# KCInput_Attenuator_V0_2.net
KiCad netlist of a schematic drawn in Altium Designer
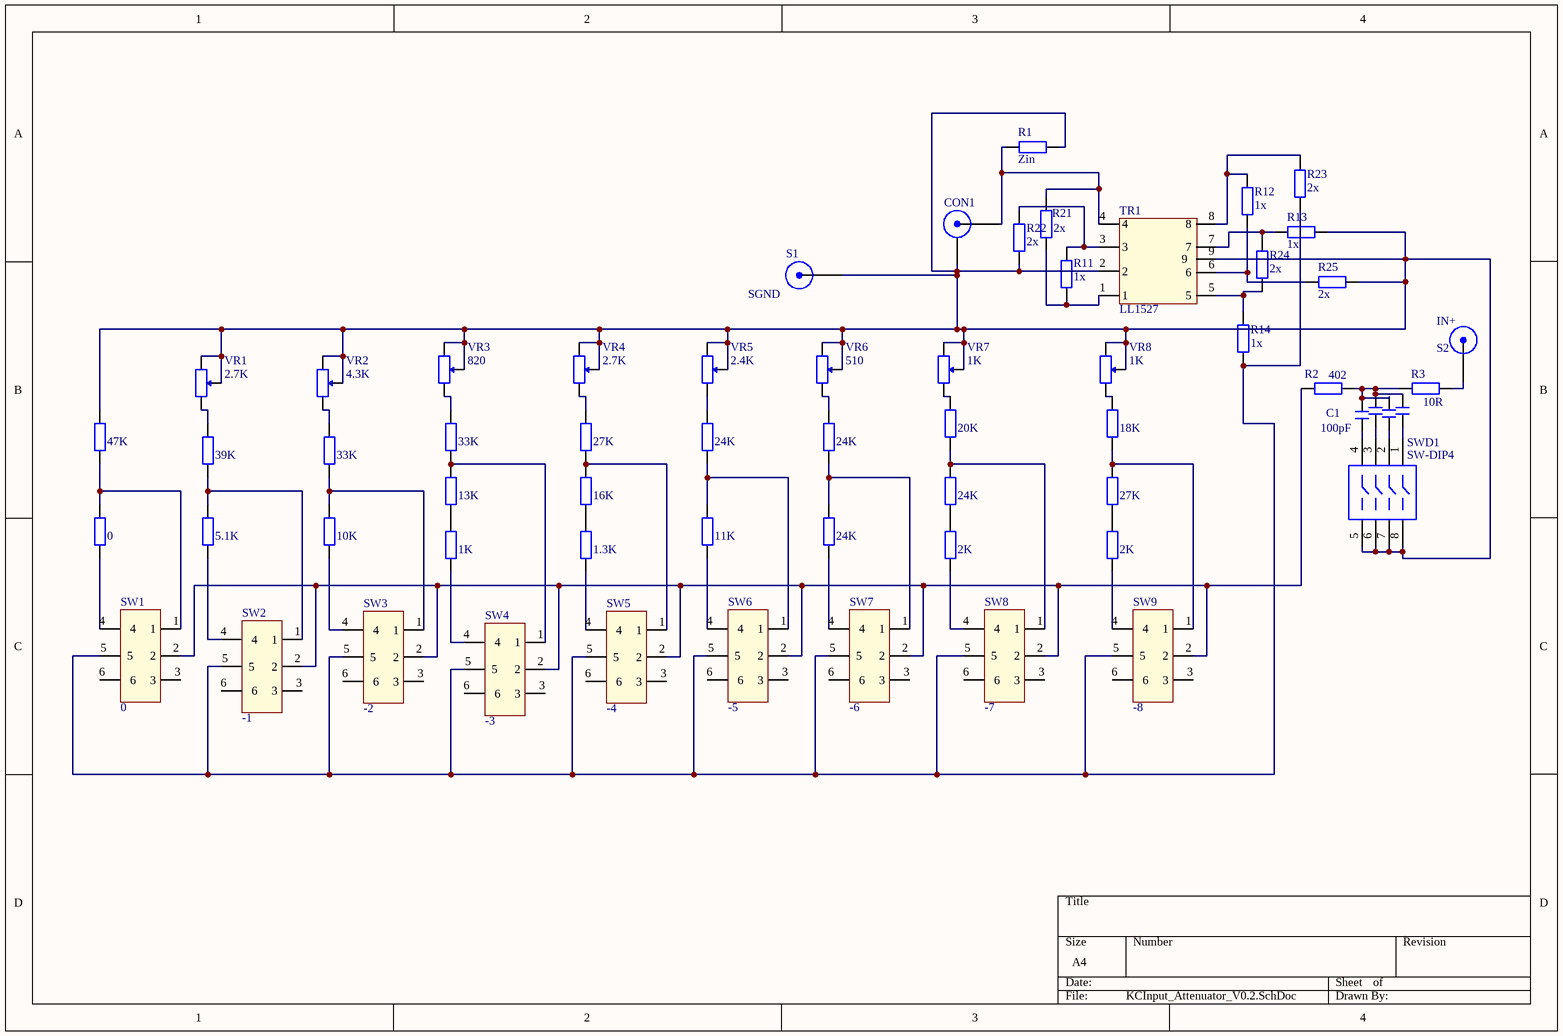
[diagram p0: KCInput_Attenuator_V0.2.SchDoc]

(export (version "E")
  (design (tool "Eeschema 10.0.6"))
  (components
    (comp (ref "C1")
      (value "100pF")
      (footprint "CBB 6.3*6.3*5")
      (description "CBB电容")
      (fields (field (name "版权归属") "源创客"))
      (libsource (lib "电阻-电容-电感") (part "C-CBB"))
    )
    (comp (ref "C2")
      (value "100pF")
      (footprint "CBB 6.3*6.3*5")
      (description "CBB电容")
      (fields (field (name "版权归属") "源创客"))
      (libsource (lib "电阻-电容-电感") (part "C-CBB"))
    )
    (comp (ref "C3")
      (value "100pF")
      (footprint "CBB 6.3*6.3*5")
      (description "CBB电容")
      (fields (field (name "版权归属") "源创客"))
      (libsource (lib "电阻-电容-电感") (part "C-CBB"))
    )
    (comp (ref "C4")
      (value "20pF")
      (footprint "CBB 6.3*6.3*5")
      (description "CBB电容")
      (fields (field (name "版权归属") "源创客"))
      (libsource (lib "电阻-电容-电感") (part "C-CBB"))
    )
    (comp (ref "CON1")
      (value "RCA")
      (footprint "RCA-RJ255")
      (description "RCA Connector")
      (fields (field (name "PUBLISHER") "Altium Limited"))
      (libsource (lib "Connectors") (part "RCA"))
    )
    (comp (ref "R1")
      (value "Zin")
      (footprint "RS 1/4W")
      (description "直插色环电阻")
      (fields (field (name "版权归属") "源创客"))
      (libsource (lib "电阻-电容-电感") (part "R-CRR"))
    )
    (comp (ref "R2")
      (value "402")
      (footprint "RS 1/4W")
      (description "直插色环电阻")
      (fields (field (name "版权归属") "源创客"))
      (libsource (lib "电阻-电容-电感") (part "R-CRR"))
    )
    (comp (ref "R3")
      (value "10R")
      (footprint "RS 1/4W")
      (description "直插色环电阻")
      (fields (field (name "版权归属") "源创客"))
      (libsource (lib "电阻-电容-电感") (part "R-CRR"))
    )
    (comp (ref "R11")
      (value "1x")
      (footprint "RS 1/4W")
      (description "直插色环电阻")
      (fields (field (name "版权归属") "源创客"))
      (libsource (lib "电阻-电容-电感") (part "R-CRR"))
    )
    (comp (ref "R12")
      (value "1x")
      (footprint "RS 1/4W")
      (description "直插色环电阻")
      (fields (field (name "版权归属") "源创客"))
      (libsource (lib "电阻-电容-电感") (part "R-CRR"))
    )
    (comp (ref "R13")
      (value "1x")
      (footprint "RS 1/4W")
      (description "直插色环电阻")
      (fields (field (name "版权归属") "源创客"))
      (libsource (lib "电阻-电容-电感") (part "R-CRR"))
    )
    (comp (ref "R14")
      (value "1x")
      (footprint "RS 1/4W")
      (description "直插色环电阻")
      (fields (field (name "版权归属") "源创客"))
      (libsource (lib "电阻-电容-电感") (part "R-CRR"))
    )
    (comp (ref "R21")
      (value "2x")
      (footprint "RS 1/4W")
      (description "直插色环电阻")
      (fields (field (name "版权归属") "源创客"))
      (libsource (lib "电阻-电容-电感") (part "R-CRR"))
    )
    (comp (ref "R22")
      (value "2x")
      (footprint "RS 1/4W")
      (description "直插色环电阻")
      (fields (field (name "版权归属") "源创客"))
      (libsource (lib "电阻-电容-电感") (part "R-CRR"))
    )
    (comp (ref "R23")
      (value "2x")
      (footprint "RS 1/4W")
      (description "直插色环电阻")
      (fields (field (name "版权归属") "源创客"))
      (libsource (lib "电阻-电容-电感") (part "R-CRR"))
    )
    (comp (ref "R24")
      (value "2x")
      (footprint "RS 1/4W")
      (description "直插色环电阻")
      (fields (field (name "版权归属") "源创客"))
      (libsource (lib "电阻-电容-电感") (part "R-CRR"))
    )
    (comp (ref "R25")
      (value "2x")
      (footprint "RS 1/4W")
      (description "直插色环电阻")
      (fields (field (name "版权归属") "源创客"))
      (libsource (lib "电阻-电容-电感") (part "R-CRR"))
    )
    (comp (ref "R41")
      (value "0")
      (footprint "RS 1/4W")
      (description "直插色环电阻")
      (fields (field (name "版权归属") "源创客"))
      (libsource (lib "电阻-电容-电感") (part "R-CRR"))
    )
    (comp (ref "R42")
      (value "47K")
      (footprint "RS 1/4W")
      (description "直插色环电阻")
      (fields (field (name "版权归属") "源创客"))
      (libsource (lib "电阻-电容-电感") (part "R-CRR"))
    )
    (comp (ref "R43")
      (value "5.1K")
      (footprint "RS 1/4W")
      (description "直插色环电阻")
      (fields (field (name "版权归属") "源创客"))
      (libsource (lib "电阻-电容-电感") (part "R-CRR"))
    )
    (comp (ref "R44")
      (value "39K")
      (footprint "RS 1/4W")
      (description "直插色环电阻")
      (fields (field (name "版权归属") "源创客"))
      (libsource (lib "电阻-电容-电感") (part "R-CRR"))
    )
    (comp (ref "R45")
      (value "10K")
      (footprint "RS 1/4W")
      (description "直插色环电阻")
      (fields (field (name "版权归属") "源创客"))
      (libsource (lib "电阻-电容-电感") (part "R-CRR"))
    )
    (comp (ref "R46")
      (value "33K")
      (footprint "RS 1/4W")
      (description "直插色环电阻")
      (fields (field (name "版权归属") "源创客"))
      (libsource (lib "电阻-电容-电感") (part "R-CRR"))
    )
    (comp (ref "R47")
      (value "13K")
      (footprint "RS 1/4W")
      (description "直插色环电阻")
      (fields (field (name "版权归属") "源创客"))
      (libsource (lib "电阻-电容-电感") (part "R-CRR"))
    )
    (comp (ref "R48")
      (value "33K")
      (footprint "RS 1/4W")
      (description "直插色环电阻")
      (fields (field (name "版权归属") "源创客"))
      (libsource (lib "电阻-电容-电感") (part "R-CRR"))
    )
    (comp (ref "R49")
      (value "16K")
      (footprint "RS 1/4W")
      (description "直插色环电阻")
      (fields (field (name "版权归属") "源创客"))
      (libsource (lib "电阻-电容-电感") (part "R-CRR"))
    )
    (comp (ref "R50")
      (value "27K")
      (footprint "RS 1/4W")
      (description "直插色环电阻")
      (fields (field (name "版权归属") "源创客"))
      (libsource (lib "电阻-电容-电感") (part "R-CRR"))
    )
    (comp (ref "R51")
      (value "11K")
      (footprint "RS 1/4W")
      (description "直插色环电阻")
      (fields (field (name "版权归属") "源创客"))
      (libsource (lib "电阻-电容-电感") (part "R-CRR"))
    )
    (comp (ref "R52")
      (value "24K")
      (footprint "RS 1/4W")
      (description "直插色环电阻")
      (fields (field (name "版权归属") "源创客"))
      (libsource (lib "电阻-电容-电感") (part "R-CRR"))
    )
    (comp (ref "R53")
      (value "24K")
      (footprint "RS 1/4W")
      (description "直插色环电阻")
      (fields (field (name "版权归属") "源创客"))
      (libsource (lib "电阻-电容-电感") (part "R-CRR"))
    )
    (comp (ref "R54")
      (value "24K")
      (footprint "RS 1/4W")
      (description "直插色环电阻")
      (fields (field (name "版权归属") "源创客"))
      (libsource (lib "电阻-电容-电感") (part "R-CRR"))
    )
    (comp (ref "R55")
      (value "24K")
      (footprint "RS 1/4W")
      (description "直插色环电阻")
      (fields (field (name "版权归属") "源创客"))
      (libsource (lib "电阻-电容-电感") (part "R-CRR"))
    )
    (comp (ref "R56")
      (value "20K")
      (footprint "RS 1/4W")
      (description "直插色环电阻")
      (fields (field (name "版权归属") "源创客"))
      (libsource (lib "电阻-电容-电感") (part "R-CRR"))
    )
    (comp (ref "R57")
      (value "27K")
      (footprint "RS 1/4W")
      (description "直插色环电阻")
      (fields (field (name "版权归属") "源创客"))
      (libsource (lib "电阻-电容-电感") (part "R-CRR"))
    )
    (comp (ref "R58")
      (value "18K")
      (footprint "RS 1/4W")
      (description "直插色环电阻")
      (fields (field (name "版权归属") "源创客"))
      (libsource (lib "电阻-电容-电感") (part "R-CRR"))
    )
    (comp (ref "R471")
      (value "1K")
      (footprint "RS 1/4W")
      (description "直插色环电阻")
      (fields (field (name "版权归属") "源创客"))
      (libsource (lib "电阻-电容-电感") (part "R-CRR"))
    )
    (comp (ref "R491")
      (value "1.3K")
      (footprint "RS 1/4W")
      (description "直插色环电阻")
      (fields (field (name "版权归属") "源创客"))
      (libsource (lib "电阻-电容-电感") (part "R-CRR"))
    )
    (comp (ref "R551")
      (value "2K")
      (footprint "RS 1/4W")
      (description "直插色环电阻")
      (fields (field (name "版权归属") "源创客"))
      (libsource (lib "电阻-电容-电感") (part "R-CRR"))
    )
    (comp (ref "R571")
      (value "2K")
      (footprint "RS 1/4W")
      (description "直插色环电阻")
      (fields (field (name "版权归属") "源创客"))
      (libsource (lib "电阻-电容-电感") (part "R-CRR"))
    )
    (comp (ref "S1")
      (value "SGND")
      (footprint "Screw-M2-s")
      (description "Screw Connector")
      (libsource (lib "Connectors") (part "ScrewConnector"))
    )
    (comp (ref "S2")
      (value "IN+")
      (footprint "Screw-M2-s")
      (description "Screw Connector")
      (libsource (lib "Connectors") (part "ScrewConnector"))
    )
    (comp (ref "SW1")
      (value "0")
      (footprint "Swich_3x2")
      (description "Switch 3 pin 2 level")
      (libsource (lib "KC_amp") (part "Switch_3x2"))
    )
    (comp (ref "SW2")
      (value "-1")
      (footprint "Swich_3x2")
      (description "Switch 3 pin 2 level")
      (libsource (lib "KC_amp") (part "Switch_3x2"))
    )
    (comp (ref "SW3")
      (value "-2")
      (footprint "Swich_3x2")
      (description "Switch 3 pin 2 level")
      (libsource (lib "KC_amp") (part "Switch_3x2"))
    )
    (comp (ref "SW4")
      (value "-3")
      (footprint "Swich_3x2")
      (description "Switch 3 pin 2 level")
      (libsource (lib "KC_amp") (part "Switch_3x2"))
    )
    (comp (ref "SW5")
      (value "-4")
      (footprint "Swich_3x2")
      (description "Switch 3 pin 2 level")
      (libsource (lib "KC_amp") (part "Switch_3x2"))
    )
    (comp (ref "SW6")
      (value "-5")
      (footprint "Swich_3x2")
      (description "Switch 3 pin 2 level")
      (libsource (lib "KC_amp") (part "Switch_3x2"))
    )
    (comp (ref "SW7")
      (value "-6")
      (footprint "Swich_3x2")
      (description "Switch 3 pin 2 level")
      (libsource (lib "KC_amp") (part "Switch_3x2"))
    )
    (comp (ref "SW8")
      (value "-7")
      (footprint "Swich_3x2")
      (description "Switch 3 pin 2 level")
      (libsource (lib "KC_amp") (part "Switch_3x2"))
    )
    (comp (ref "SW9")
      (value "-8")
      (footprint "Swich_3x2")
      (description "Switch 3 pin 2 level")
      (libsource (lib "KC_amp") (part "Switch_3x2"))
    )
    (comp (ref "SWD1")
      (value "SW-DIP4")
      (footprint "DIP-8")
      (description "DIP Switch")
      (fields (field (name "PUBLISHER") "Altium Limited"))
      (libsource (lib "Miscellaneous Devices") (part "SW-DIP4"))
    )
    (comp (ref "TR1")
      (value "LL1527")
      (footprint "LL1527")
      (description "Lundahl LL1527")
      (libsource (lib "KC_amp") (part "LL1527"))
    )
    (comp (ref "VR1")
      (value "2.7K")
      (footprint "RS 1/2W-VR")
      (description "直插可调电阻-顶调")
      (libsource (lib "电阻-电容-电感") (part "VR-W"))
    )
    (comp (ref "VR2")
      (value "4.3K")
      (footprint "RS 1/2W-VR")
      (description "直插可调电阻-顶调")
      (libsource (lib "电阻-电容-电感") (part "VR-W"))
    )
    (comp (ref "VR3")
      (value "820")
      (footprint "RS 1/2W-VR")
      (description "直插可调电阻-顶调")
      (libsource (lib "电阻-电容-电感") (part "VR-W"))
    )
    (comp (ref "VR4")
      (value "2.7K")
      (footprint "RS 1/2W-VR")
      (description "直插可调电阻-顶调")
      (libsource (lib "电阻-电容-电感") (part "VR-W"))
    )
    (comp (ref "VR5")
      (value "2.4K")
      (footprint "RS 1/2W-VR")
      (description "直插可调电阻-顶调")
      (libsource (lib "电阻-电容-电感") (part "VR-W"))
    )
    (comp (ref "VR6")
      (value "510")
      (footprint "RS 1/2W-VR")
      (description "直插可调电阻-顶调")
      (libsource (lib "电阻-电容-电感") (part "VR-W"))
    )
    (comp (ref "VR7")
      (value "1K")
      (footprint "RS 1/2W-VR")
      (description "直插可调电阻-顶调")
      (libsource (lib "电阻-电容-电感") (part "VR-W"))
    )
    (comp (ref "VR8")
      (value "1K")
      (footprint "RS 1/2W-VR")
      (description "直插可调电阻-顶调")
      (libsource (lib "电阻-电容-电感") (part "VR-W"))
    )
  )
  (nets
    (net (code "1") (name "Net-(C1-Pad1)") (class "Default")
      (node (ref "C1") (pin "1") (pinfunction "1_1") (pintype "passive"))
      (node (ref "SWD1") (pin "4") (pinfunction "4_4") (pintype "passive"))
    )
    (net (code "2") (name "Net-(C1-Pad2)") (class "Default")
      (node (ref "C1") (pin "2") (pinfunction "2_2") (pintype "passive"))
      (node (ref "C2") (pin "2") (pinfunction "2_2") (pintype "passive"))
      (node (ref "C3") (pin "2") (pinfunction "2_2") (pintype "passive"))
      (node (ref "C4") (pin "2") (pinfunction "2_2") (pintype "passive"))
      (node (ref "R2") (pin "2") (pinfunction "2_2") (pintype "passive"))
      (node (ref "R3") (pin "1") (pinfunction "1_1") (pintype "passive"))
    )
    (net (code "3") (name "Net-(C2-Pad1)") (class "Default")
      (node (ref "C2") (pin "1") (pinfunction "1_1") (pintype "passive"))
      (node (ref "SWD1") (pin "3") (pinfunction "3_3") (pintype "passive"))
    )
    (net (code "4") (name "Net-(C3-Pad1)") (class "Default")
      (node (ref "C3") (pin "1") (pinfunction "1_1") (pintype "passive"))
      (node (ref "SWD1") (pin "2") (pinfunction "2_2") (pintype "passive"))
    )
    (net (code "5") (name "Net-(C4-Pad1)") (class "Default")
      (node (ref "C4") (pin "1") (pinfunction "1_1") (pintype "passive"))
      (node (ref "SWD1") (pin "1") (pinfunction "1_1") (pintype "passive"))
    )
    (net (code "6") (name "Net-(CON1-X)") (class "Default")
      (node (ref "CON1") (pin "1") (pinfunction "X_1") (pintype "passive"))
      (node (ref "R1") (pin "1") (pinfunction "1_1") (pintype "passive"))
      (node (ref "R21") (pin "2") (pinfunction "2_2") (pintype "passive"))
      (node (ref "TR1") (pin "4") (pinfunction "4_4") (pintype "passive"))
    )
    (net (code "7") (name "Net-(CON1-Y)") (class "Default")
      (node (ref "CON1") (pin "2") (pinfunction "Y_2") (pintype "passive"))
      (node (ref "R1") (pin "2") (pinfunction "2_2") (pintype "passive"))
      (node (ref "R13") (pin "2") (pinfunction "2_2") (pintype "passive"))
      (node (ref "R22") (pin "1") (pinfunction "1_1") (pintype "passive"))
      (node (ref "R25") (pin "2") (pinfunction "2_2") (pintype "passive"))
      (node (ref "R42") (pin "2") (pinfunction "2_2") (pintype "passive"))
      (node (ref "S1") (pin "1") (pinfunction "X_1") (pintype "passive"))
      (node (ref "SWD1") (pin "5") (pinfunction "5_5") (pintype "passive"))
      (node (ref "SWD1") (pin "6") (pinfunction "6_6") (pintype "passive"))
      (node (ref "SWD1") (pin "7") (pinfunction "7_7") (pintype "passive"))
      (node (ref "SWD1") (pin "8") (pinfunction "8_8") (pintype "passive"))
      (node (ref "TR1") (pin "2") (pinfunction "2_2") (pintype "passive"))
      (node (ref "TR1") (pin "9") (pinfunction "9_9") (pintype "passive"))
      (node (ref "VR1") (pin "1") (pinfunction "1_1") (pintype "passive"))
      (node (ref "VR1") (pin "3") (pinfunction "3_3") (pintype "passive"))
      (node (ref "VR2") (pin "1") (pinfunction "1_1") (pintype "passive"))
      (node (ref "VR2") (pin "3") (pinfunction "3_3") (pintype "passive"))
      (node (ref "VR3") (pin "1") (pinfunction "1_1") (pintype "passive"))
      (node (ref "VR3") (pin "3") (pinfunction "3_3") (pintype "passive"))
      (node (ref "VR4") (pin "1") (pinfunction "1_1") (pintype "passive"))
      (node (ref "VR4") (pin "3") (pinfunction "3_3") (pintype "passive"))
      (node (ref "VR5") (pin "1") (pinfunction "1_1") (pintype "passive"))
      (node (ref "VR5") (pin "3") (pinfunction "3_3") (pintype "passive"))
      (node (ref "VR6") (pin "1") (pinfunction "1_1") (pintype "passive"))
      (node (ref "VR6") (pin "3") (pinfunction "3_3") (pintype "passive"))
      (node (ref "VR7") (pin "1") (pinfunction "1_1") (pintype "passive"))
      (node (ref "VR7") (pin "3") (pinfunction "3_3") (pintype "passive"))
      (node (ref "VR8") (pin "1") (pinfunction "1_1") (pintype "passive"))
      (node (ref "VR8") (pin "3") (pinfunction "3_3") (pintype "passive"))
    )
    (net (code "8") (name "Net-(R2-Pad1)") (class "Default")
      (node (ref "R2") (pin "1") (pinfunction "1_1") (pintype "passive"))
      (node (ref "SW1") (pin "2") (pinfunction "2_2") (pintype "passive"))
      (node (ref "SW2") (pin "2") (pinfunction "2_2") (pintype "passive"))
      (node (ref "SW3") (pin "2") (pinfunction "2_2") (pintype "passive"))
      (node (ref "SW4") (pin "2") (pinfunction "2_2") (pintype "passive"))
      (node (ref "SW5") (pin "2") (pinfunction "2_2") (pintype "passive"))
      (node (ref "SW6") (pin "2") (pinfunction "2_2") (pintype "passive"))
      (node (ref "SW7") (pin "2") (pinfunction "2_2") (pintype "passive"))
      (node (ref "SW8") (pin "2") (pinfunction "2_2") (pintype "passive"))
      (node (ref "SW9") (pin "2") (pinfunction "2_2") (pintype "passive"))
    )
    (net (code "9") (name "Net-(R11-Pad1)") (class "Default")
      (node (ref "R11") (pin "1") (pinfunction "1_1") (pintype "passive"))
      (node (ref "R21") (pin "1") (pinfunction "1_1") (pintype "passive"))
      (node (ref "TR1") (pin "1") (pinfunction "1_1") (pintype "passive"))
    )
    (net (code "10") (name "Net-(R11-Pad2)") (class "Default")
      (node (ref "R11") (pin "2") (pinfunction "2_2") (pintype "passive"))
      (node (ref "R22") (pin "2") (pinfunction "2_2") (pintype "passive"))
      (node (ref "TR1") (pin "3") (pinfunction "3_3") (pintype "passive"))
    )
    (net (code "11") (name "Net-(R12-Pad1)") (class "Default")
      (node (ref "R12") (pin "1") (pinfunction "1_1") (pintype "passive"))
      (node (ref "R25") (pin "1") (pinfunction "1_1") (pintype "passive"))
      (node (ref "TR1") (pin "6") (pinfunction "6_6") (pintype "passive"))
    )
    (net (code "12") (name "Net-(R12-Pad2)") (class "Default")
      (node (ref "R12") (pin "2") (pinfunction "2_2") (pintype "passive"))
      (node (ref "R23") (pin "2") (pinfunction "2_2") (pintype "passive"))
      (node (ref "TR1") (pin "8") (pinfunction "8_8") (pintype "passive"))
    )
    (net (code "13") (name "Net-(R13-Pad1)") (class "Default")
      (node (ref "R13") (pin "1") (pinfunction "1_1") (pintype "passive"))
      (node (ref "R24") (pin "2") (pinfunction "2_2") (pintype "passive"))
      (node (ref "TR1") (pin "7") (pinfunction "7_7") (pintype "passive"))
    )
    (net (code "14") (name "Net-(R14-Pad1)") (class "Default")
      (node (ref "R14") (pin "1") (pinfunction "1_1") (pintype "passive"))
      (node (ref "R23") (pin "1") (pinfunction "1_1") (pintype "passive"))
      (node (ref "SW1") (pin "5") (pinfunction "5_5") (pintype "passive"))
      (node (ref "SW2") (pin "5") (pinfunction "5_5") (pintype "passive"))
      (node (ref "SW3") (pin "5") (pinfunction "5_5") (pintype "passive"))
      (node (ref "SW4") (pin "5") (pinfunction "5_5") (pintype "passive"))
      (node (ref "SW5") (pin "5") (pinfunction "5_5") (pintype "passive"))
      (node (ref "SW6") (pin "5") (pinfunction "5_5") (pintype "passive"))
      (node (ref "SW7") (pin "5") (pinfunction "5_5") (pintype "passive"))
      (node (ref "SW8") (pin "5") (pinfunction "5_5") (pintype "passive"))
      (node (ref "SW9") (pin "5") (pinfunction "5_5") (pintype "passive"))
    )
    (net (code "15") (name "Net-(R14-Pad2)") (class "Default")
      (node (ref "R14") (pin "2") (pinfunction "2_2") (pintype "passive"))
      (node (ref "R24") (pin "1") (pinfunction "1_1") (pintype "passive"))
      (node (ref "TR1") (pin "5") (pinfunction "5_5") (pintype "passive"))
    )
    (net (code "16") (name "Net-(R41-Pad1)") (class "Default")
      (node (ref "R41") (pin "1") (pinfunction "1_1") (pintype "passive"))
      (node (ref "SW1") (pin "4") (pinfunction "4_4") (pintype "passive"))
    )
    (net (code "17") (name "Net-(R41-Pad2)") (class "Default")
      (node (ref "R41") (pin "2") (pinfunction "2_2") (pintype "passive"))
      (node (ref "R42") (pin "1") (pinfunction "1_1") (pintype "passive"))
      (node (ref "SW1") (pin "1") (pinfunction "1_1") (pintype "passive"))
    )
    (net (code "18") (name "Net-(R43-Pad1)") (class "Default")
      (node (ref "R43") (pin "1") (pinfunction "1_1") (pintype "passive"))
      (node (ref "SW2") (pin "4") (pinfunction "4_4") (pintype "passive"))
    )
    (net (code "19") (name "Net-(R43-Pad2)") (class "Default")
      (node (ref "R43") (pin "2") (pinfunction "2_2") (pintype "passive"))
      (node (ref "R44") (pin "1") (pinfunction "1_1") (pintype "passive"))
      (node (ref "SW2") (pin "1") (pinfunction "1_1") (pintype "passive"))
    )
    (net (code "20") (name "Net-(R44-Pad2)") (class "Default")
      (node (ref "R44") (pin "2") (pinfunction "2_2") (pintype "passive"))
      (node (ref "VR1") (pin "2") (pinfunction "2_2") (pintype "passive"))
    )
    (net (code "21") (name "Net-(R45-Pad1)") (class "Default")
      (node (ref "R45") (pin "1") (pinfunction "1_1") (pintype "passive"))
      (node (ref "SW3") (pin "4") (pinfunction "4_4") (pintype "passive"))
    )
    (net (code "22") (name "Net-(R45-Pad2)") (class "Default")
      (node (ref "R45") (pin "2") (pinfunction "2_2") (pintype "passive"))
      (node (ref "R46") (pin "1") (pinfunction "1_1") (pintype "passive"))
      (node (ref "SW3") (pin "1") (pinfunction "1_1") (pintype "passive"))
    )
    (net (code "23") (name "Net-(R46-Pad2)") (class "Default")
      (node (ref "R46") (pin "2") (pinfunction "2_2") (pintype "passive"))
      (node (ref "VR2") (pin "2") (pinfunction "2_2") (pintype "passive"))
    )
    (net (code "24") (name "Net-(R47-Pad1)") (class "Default")
      (node (ref "R47") (pin "1") (pinfunction "1_1") (pintype "passive"))
      (node (ref "R471") (pin "2") (pinfunction "2_2") (pintype "passive"))
    )
    (net (code "25") (name "Net-(R47-Pad2)") (class "Default")
      (node (ref "R47") (pin "2") (pinfunction "2_2") (pintype "passive"))
      (node (ref "R48") (pin "1") (pinfunction "1_1") (pintype "passive"))
      (node (ref "SW4") (pin "1") (pinfunction "1_1") (pintype "passive"))
    )
    (net (code "26") (name "Net-(R48-Pad2)") (class "Default")
      (node (ref "R48") (pin "2") (pinfunction "2_2") (pintype "passive"))
      (node (ref "VR3") (pin "2") (pinfunction "2_2") (pintype "passive"))
    )
    (net (code "27") (name "Net-(R49-Pad1)") (class "Default")
      (node (ref "R49") (pin "1") (pinfunction "1_1") (pintype "passive"))
      (node (ref "R491") (pin "2") (pinfunction "2_2") (pintype "passive"))
    )
    (net (code "28") (name "Net-(R49-Pad2)") (class "Default")
      (node (ref "R49") (pin "2") (pinfunction "2_2") (pintype "passive"))
      (node (ref "R50") (pin "1") (pinfunction "1_1") (pintype "passive"))
      (node (ref "SW5") (pin "1") (pinfunction "1_1") (pintype "passive"))
    )
    (net (code "29") (name "Net-(R50-Pad2)") (class "Default")
      (node (ref "R50") (pin "2") (pinfunction "2_2") (pintype "passive"))
      (node (ref "VR4") (pin "2") (pinfunction "2_2") (pintype "passive"))
    )
    (net (code "30") (name "Net-(R51-Pad1)") (class "Default")
      (node (ref "R51") (pin "1") (pinfunction "1_1") (pintype "passive"))
      (node (ref "SW6") (pin "4") (pinfunction "4_4") (pintype "passive"))
    )
    (net (code "31") (name "Net-(R51-Pad2)") (class "Default")
      (node (ref "R51") (pin "2") (pinfunction "2_2") (pintype "passive"))
      (node (ref "R52") (pin "1") (pinfunction "1_1") (pintype "passive"))
      (node (ref "SW6") (pin "1") (pinfunction "1_1") (pintype "passive"))
    )
    (net (code "32") (name "Net-(R52-Pad2)") (class "Default")
      (node (ref "R52") (pin "2") (pinfunction "2_2") (pintype "passive"))
      (node (ref "VR5") (pin "2") (pinfunction "2_2") (pintype "passive"))
    )
    (net (code "33") (name "Net-(R53-Pad1)") (class "Default")
      (node (ref "R53") (pin "1") (pinfunction "1_1") (pintype "passive"))
      (node (ref "SW7") (pin "4") (pinfunction "4_4") (pintype "passive"))
    )
    (net (code "34") (name "Net-(R53-Pad2)") (class "Default")
      (node (ref "R53") (pin "2") (pinfunction "2_2") (pintype "passive"))
      (node (ref "R54") (pin "1") (pinfunction "1_1") (pintype "passive"))
      (node (ref "SW7") (pin "1") (pinfunction "1_1") (pintype "passive"))
    )
    (net (code "35") (name "Net-(R54-Pad2)") (class "Default")
      (node (ref "R54") (pin "2") (pinfunction "2_2") (pintype "passive"))
      (node (ref "VR6") (pin "2") (pinfunction "2_2") (pintype "passive"))
    )
    (net (code "36") (name "Net-(R55-Pad1)") (class "Default")
      (node (ref "R55") (pin "1") (pinfunction "1_1") (pintype "passive"))
      (node (ref "R551") (pin "2") (pinfunction "2_2") (pintype "passive"))
    )
    (net (code "37") (name "Net-(R55-Pad2)") (class "Default")
      (node (ref "R55") (pin "2") (pinfunction "2_2") (pintype "passive"))
      (node (ref "R56") (pin "1") (pinfunction "1_1") (pintype "passive"))
      (node (ref "SW8") (pin "1") (pinfunction "1_1") (pintype "passive"))
    )
    (net (code "38") (name "Net-(R56-Pad2)") (class "Default")
      (node (ref "R56") (pin "2") (pinfunction "2_2") (pintype "passive"))
      (node (ref "VR7") (pin "2") (pinfunction "2_2") (pintype "passive"))
    )
    (net (code "39") (name "Net-(R57-Pad1)") (class "Default")
      (node (ref "R57") (pin "1") (pinfunction "1_1") (pintype "passive"))
      (node (ref "R571") (pin "2") (pinfunction "2_2") (pintype "passive"))
    )
    (net (code "40") (name "Net-(R57-Pad2)") (class "Default")
      (node (ref "R57") (pin "2") (pinfunction "2_2") (pintype "passive"))
      (node (ref "R58") (pin "1") (pinfunction "1_1") (pintype "passive"))
      (node (ref "SW9") (pin "1") (pinfunction "1_1") (pintype "passive"))
    )
    (net (code "41") (name "Net-(R58-Pad2)") (class "Default")
      (node (ref "R58") (pin "2") (pinfunction "2_2") (pintype "passive"))
      (node (ref "VR8") (pin "2") (pinfunction "2_2") (pintype "passive"))
    )
    (net (code "42") (name "Net-(R471-Pad1)") (class "Default")
      (node (ref "R471") (pin "1") (pinfunction "1_1") (pintype "passive"))
      (node (ref "SW4") (pin "4") (pinfunction "4_4") (pintype "passive"))
    )
    (net (code "43") (name "Net-(R491-Pad1)") (class "Default")
      (node (ref "R491") (pin "1") (pinfunction "1_1") (pintype "passive"))
      (node (ref "SW5") (pin "4") (pinfunction "4_4") (pintype "passive"))
    )
    (net (code "44") (name "Net-(R551-Pad1)") (class "Default")
      (node (ref "R551") (pin "1") (pinfunction "1_1") (pintype "passive"))
      (node (ref "SW8") (pin "4") (pinfunction "4_4") (pintype "passive"))
    )
    (net (code "45") (name "Net-(R571-Pad1)") (class "Default")
      (node (ref "R571") (pin "1") (pinfunction "1_1") (pintype "passive"))
      (node (ref "SW9") (pin "4") (pinfunction "4_4") (pintype "passive"))
    )
    (net (code "46") (name "Net-(S2-X)") (class "Default")
      (node (ref "R3") (pin "2") (pinfunction "2_2") (pintype "passive"))
      (node (ref "S2") (pin "1") (pinfunction "X_1") (pintype "passive"))
    )
    (net (code "47") (name "unconnected-(SW1-Pad3)") (class "Default")
      (node (ref "SW1") (pin "3") (pinfunction "3_3") (pintype "passive"))
    )
    (net (code "48") (name "unconnected-(SW1-Pad6)") (class "Default")
      (node (ref "SW1") (pin "6") (pinfunction "6_6") (pintype "passive"))
    )
    (net (code "49") (name "unconnected-(SW2-Pad3)") (class "Default")
      (node (ref "SW2") (pin "3") (pinfunction "3_3") (pintype "passive"))
    )
    (net (code "50") (name "unconnected-(SW2-Pad6)") (class "Default")
      (node (ref "SW2") (pin "6") (pinfunction "6_6") (pintype "passive"))
    )
    (net (code "51") (name "unconnected-(SW3-Pad3)") (class "Default")
      (node (ref "SW3") (pin "3") (pinfunction "3_3") (pintype "passive"))
    )
    (net (code "52") (name "unconnected-(SW3-Pad6)") (class "Default")
      (node (ref "SW3") (pin "6") (pinfunction "6_6") (pintype "passive"))
    )
    (net (code "53") (name "unconnected-(SW4-Pad3)") (class "Default")
      (node (ref "SW4") (pin "3") (pinfunction "3_3") (pintype "passive"))
    )
    (net (code "54") (name "unconnected-(SW4-Pad6)") (class "Default")
      (node (ref "SW4") (pin "6") (pinfunction "6_6") (pintype "passive"))
    )
    (net (code "55") (name "unconnected-(SW5-Pad3)") (class "Default")
      (node (ref "SW5") (pin "3") (pinfunction "3_3") (pintype "passive"))
    )
    (net (code "56") (name "unconnected-(SW5-Pad6)") (class "Default")
      (node (ref "SW5") (pin "6") (pinfunction "6_6") (pintype "passive"))
    )
    (net (code "57") (name "unconnected-(SW6-Pad3)") (class "Default")
      (node (ref "SW6") (pin "3") (pinfunction "3_3") (pintype "passive"))
    )
    (net (code "58") (name "unconnected-(SW6-Pad6)") (class "Default")
      (node (ref "SW6") (pin "6") (pinfunction "6_6") (pintype "passive"))
    )
    (net (code "59") (name "unconnected-(SW7-Pad3)") (class "Default")
      (node (ref "SW7") (pin "3") (pinfunction "3_3") (pintype "passive"))
    )
    (net (code "60") (name "unconnected-(SW7-Pad6)") (class "Default")
      (node (ref "SW7") (pin "6") (pinfunction "6_6") (pintype "passive"))
    )
    (net (code "61") (name "unconnected-(SW8-Pad3)") (class "Default")
      (node (ref "SW8") (pin "3") (pinfunction "3_3") (pintype "passive"))
    )
    (net (code "62") (name "unconnected-(SW8-Pad6)") (class "Default")
      (node (ref "SW8") (pin "6") (pinfunction "6_6") (pintype "passive"))
    )
    (net (code "63") (name "unconnected-(SW9-Pad3)") (class "Default")
      (node (ref "SW9") (pin "3") (pinfunction "3_3") (pintype "passive"))
    )
    (net (code "64") (name "unconnected-(SW9-Pad6)") (class "Default")
      (node (ref "SW9") (pin "6") (pinfunction "6_6") (pintype "passive"))
    )
  )
)
